# ADC.net
KiCad netlist of a schematic drawn in Altium Designer
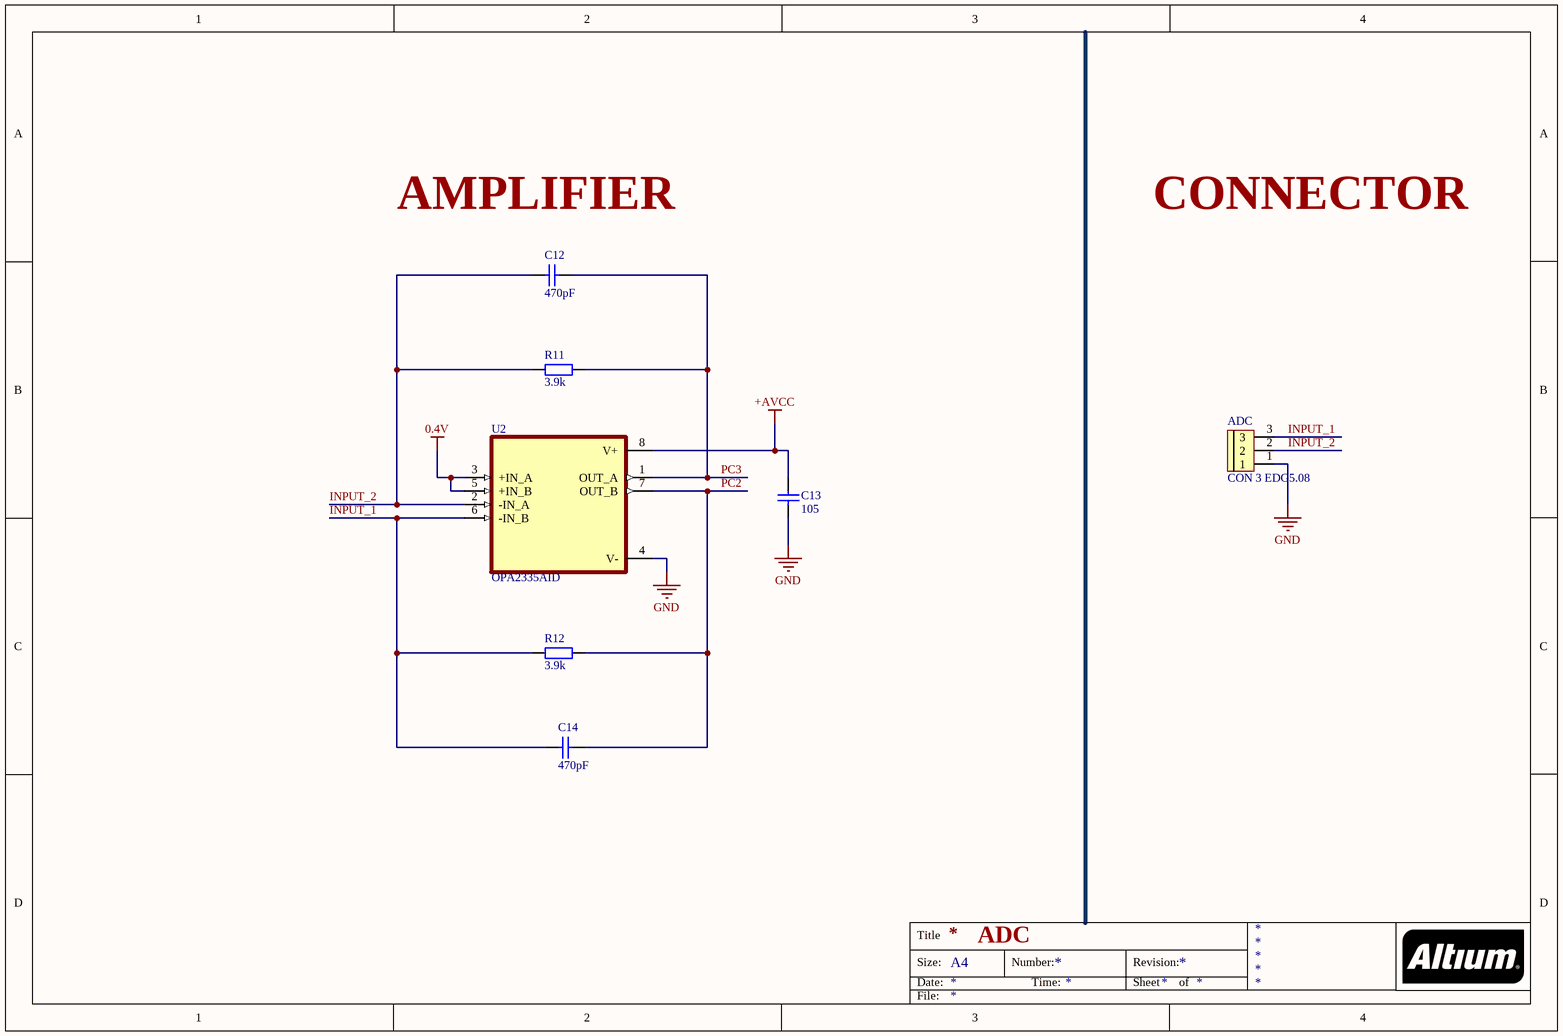
[diagram p0: ADC.SchDoc]

(export (version "E")
  (design (tool "Eeschema 10.0.6"))
  (components
    (comp (ref "ADC")
      (value "CON 3 EDG5.08")
      (footprint "CON 3 3EDG5.08")
      (description "Cắm")
      (libsource (lib "Altium_Lib_by_KhueNguyenCreator") (part "CON 3 EDG5.08"))
    )
    (comp (ref "C12")
      (value "470pF")
      (footprint "tu 0603")
      (description "Dán")
      (libsource (lib "Altium_Lib_by_KhueNguyenCreator") (part "Tu 0603 470pF 50V 10%"))
    )
    (comp (ref "C13")
      (value "105")
      (footprint "tu 1206")
      (description "Dán")
      (libsource (lib "Altium_Lib_by_KhueNguyenCreator") (part "Tu 1206 105 50V 20%"))
    )
    (comp (ref "C14")
      (value "470pF")
      (footprint "tu 0603")
      (description "Dán")
      (libsource (lib "Altium_Lib_by_KhueNguyenCreator") (part "Tu 0603 470pF 50V 10%"))
    )
    (comp (ref "R11")
      (value "3.9k")
      (footprint "tro smd 0603")
      (description "Dán")
      (libsource (lib "Altium_Lib_by_KhueNguyenCreator") (part "Tro 0603 1% 3.9k"))
    )
    (comp (ref "R12")
      (value "3.9k")
      (footprint "tro smd 0603")
      (description "Dán")
      (libsource (lib "Altium_Lib_by_KhueNguyenCreator") (part "Tro 0603 1% 3.9k"))
    )
    (comp (ref "U2")
      (value "OPA2335AID")
      (footprint "SOIC127P599X175-8N")
      (fields (field (name "MF") "{'manufacturer': u'Texas Instruments'}"))
      (libsource (lib "SnapEDA_Library") (part "OPA2335AID"))
    )
  )
  (nets
    (net (code "1") (name "+AVCC") (class "Default")
      (node (ref "C13") (pin "1") (pinfunction "1_1") (pintype "passive"))
      (node (ref "U2") (pin "8") (pinfunction "V+_8") (pintype "power_in"))
    )
    (net (code "2") (name "/INPUT_1") (class "Default")
      (node (ref "ADC") (pin "3") (pinfunction "3_3") (pintype "passive"))
      (node (ref "C14") (pin "2") (pinfunction "2_2") (pintype "passive"))
      (node (ref "R12") (pin "1") (pinfunction "1_1") (pintype "passive"))
      (node (ref "U2") (pin "6") (pinfunction "-IN_B_6") (pintype "input"))
    )
    (net (code "3") (name "/INPUT_2") (class "Default")
      (node (ref "ADC") (pin "2") (pinfunction "2_2") (pintype "passive"))
      (node (ref "C12") (pin "2") (pinfunction "2_2") (pintype "passive"))
      (node (ref "R11") (pin "1") (pinfunction "1_1") (pintype "passive"))
      (node (ref "U2") (pin "2") (pinfunction "-IN_A_2") (pintype "input"))
    )
    (net (code "4") (name "/PC2") (class "Default")
      (node (ref "C14") (pin "1") (pinfunction "1_1") (pintype "passive"))
      (node (ref "R12") (pin "2") (pinfunction "2_2") (pintype "passive"))
      (node (ref "U2") (pin "7") (pinfunction "OUT_B_7") (pintype "output"))
    )
    (net (code "5") (name "/PC3") (class "Default")
      (node (ref "C12") (pin "1") (pinfunction "1_1") (pintype "passive"))
      (node (ref "R11") (pin "2") (pinfunction "2_2") (pintype "passive"))
      (node (ref "U2") (pin "1") (pinfunction "OUT_A_1") (pintype "output"))
    )
    (net (code "6") (name "0.4V") (class "Default")
      (node (ref "U2") (pin "3") (pinfunction "+IN_A_3") (pintype "input"))
      (node (ref "U2") (pin "5") (pinfunction "+IN_B_5") (pintype "input"))
    )
    (net (code "7") (name "GND") (class "Default")
      (node (ref "ADC") (pin "1") (pinfunction "1_1") (pintype "passive"))
      (node (ref "C13") (pin "2") (pinfunction "2_2") (pintype "passive"))
      (node (ref "U2") (pin "4") (pinfunction "V-_4") (pintype "power_in"))
    )
  )
)
